# COMS0004_3_RadioMux.net
KiCad netlist of a schematic drawn in Altium Designer
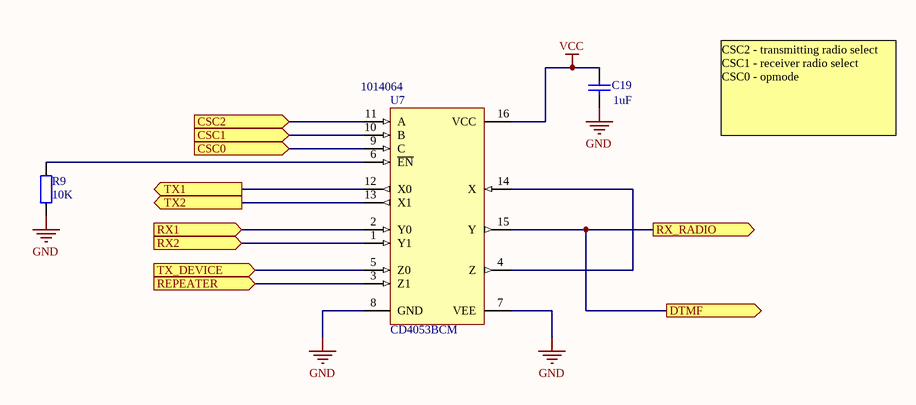
[diagram p0: COMS0004_3_RadioMux.SchDoc]

(export (version "E")
  (design (tool "Eeschema 10.0.6"))
  (components
    (comp (ref "C19")
      (value "1uF")
      (footprint "0805")
      (description "Capacitor")
      (fields (field (name "Comment") "C1210") (field (name "PUBLISHER") "Altium Limited"))
      (libsource (lib "Miscellaneous Devices") (part "Cap"))
    )
    (comp (ref "R9")
      (value "10K")
      (footprint "RESC2012N")
      (description "Resistor")
      (fields (field (name "Comment") "Res1") (field (name "PUBLISHER") "Altium Limited"))
      (libsource (lib "Miscellaneous Devices") (part "Res2"))
    )
    (comp (ref "U7")
      (value "CD4053BCM")
      (footprint "M16A_M")
      (description "Triple 2-Channnel Analog Multiplexer/Demutiplexer")
      (fields (field (name "SUPPLIER PART NUMBER 1") "1014064") (field (name "PUBLISHER") "Altium Limited"))
      (libsource (lib "FSC Logic Multiplexer") (part "CD4053BCM"))
    )
  )
  (nets
    (net (code "1") (name "/CSC0") (class "Default")
      (node (ref "U7") (pin "9") (pinfunction "C_9") (pintype "input"))
    )
    (net (code "2") (name "/CSC1") (class "Default")
      (node (ref "U7") (pin "10") (pinfunction "B_10") (pintype "input"))
    )
    (net (code "3") (name "/CSC2") (class "Default")
      (node (ref "U7") (pin "11") (pinfunction "A_11") (pintype "input"))
    )
    (net (code "4") (name "/DTMF") (class "Default")
      (node (ref "U7") (pin "15") (pinfunction "Y_15") (pintype "output"))
    )
    (net (code "5") (name "/REPEATER") (class "Default")
      (node (ref "U7") (pin "3") (pinfunction "Z1_3") (pintype "input"))
    )
    (net (code "6") (name "/RX1") (class "Default")
      (node (ref "U7") (pin "2") (pinfunction "Y0_2") (pintype "input"))
    )
    (net (code "7") (name "/RX2") (class "Default")
      (node (ref "U7") (pin "1") (pinfunction "Y1_1") (pintype "input"))
    )
    (net (code "8") (name "/TX1") (class "Default")
      (node (ref "U7") (pin "12") (pinfunction "X0_12") (pintype "output"))
    )
    (net (code "9") (name "/TX2") (class "Default")
      (node (ref "U7") (pin "13") (pinfunction "X1_13") (pintype "output"))
    )
    (net (code "10") (name "/TX_DEVICE") (class "Default")
      (node (ref "U7") (pin "5") (pinfunction "Z0_5") (pintype "input"))
    )
    (net (code "11") (name "GND") (class "Default")
      (node (ref "C19") (pin "1") (pinfunction "1_1") (pintype "passive"))
      (node (ref "R9") (pin "2") (pinfunction "2_2") (pintype "passive"))
      (node (ref "U7") (pin "7") (pinfunction "VEE_7") (pintype "power_in"))
      (node (ref "U7") (pin "8") (pinfunction "GND_8") (pintype "power_in"))
    )
    (net (code "12") (name "Net-(U7-X)") (class "Default")
      (node (ref "U7") (pin "14") (pinfunction "X_14") (pintype "input"))
      (node (ref "U7") (pin "4") (pinfunction "Z_4") (pintype "output"))
    )
    (net (code "13") (name "Net-(U7-~{EN})") (class "Default")
      (node (ref "R9") (pin "1") (pinfunction "1_1") (pintype "passive"))
      (node (ref "U7") (pin "6") (pinfunction "~{EN}_6") (pintype "input"))
    )
    (net (code "14") (name "VCC") (class "Default")
      (node (ref "C19") (pin "2") (pinfunction "2_2") (pintype "passive"))
      (node (ref "U7") (pin "16") (pinfunction "VCC_16") (pintype "power_in"))
    )
  )
)
